# JETSON_V2.net
KiCad netlist of a schematic drawn in Altium Designer
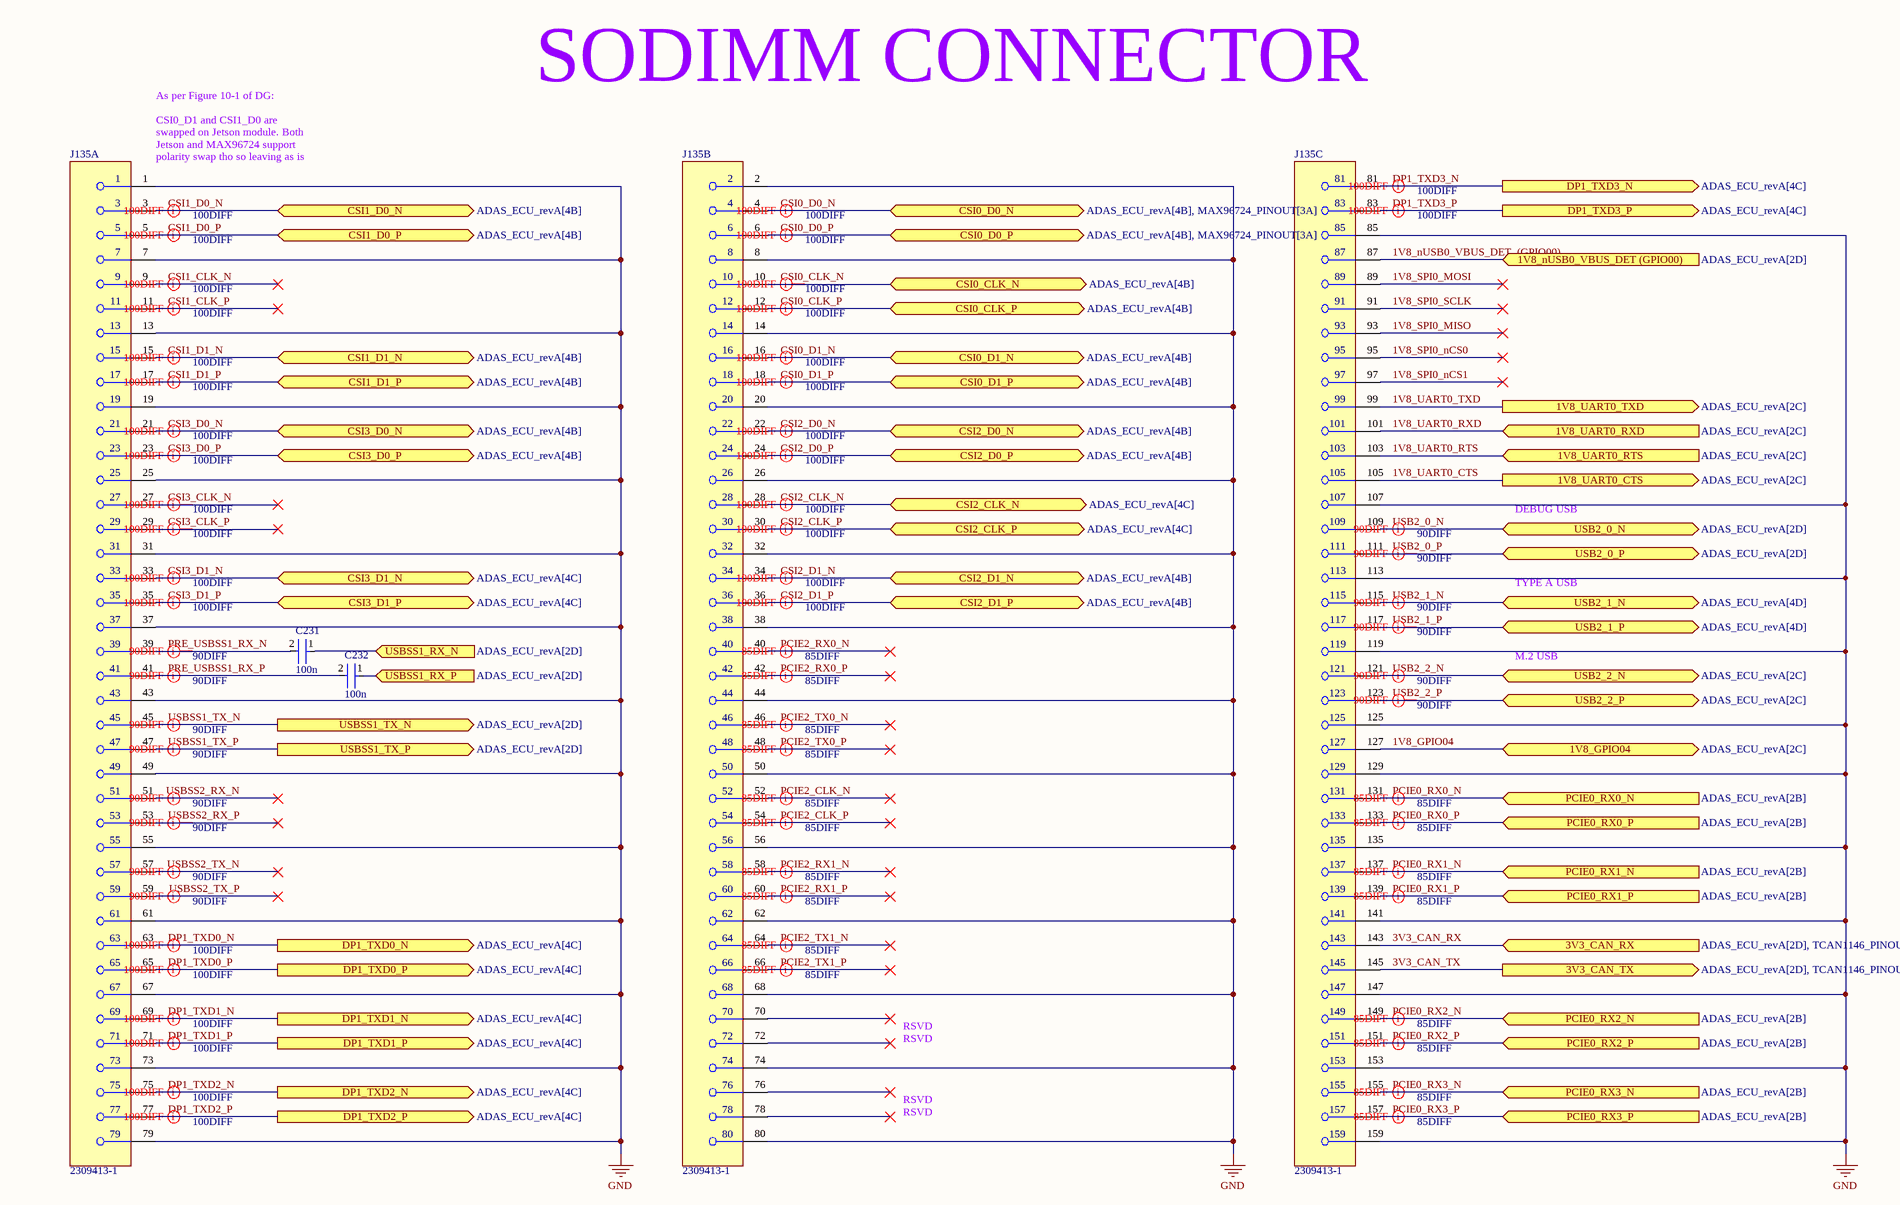
[diagram p0: JETSON_V2.SchDoc, top left]
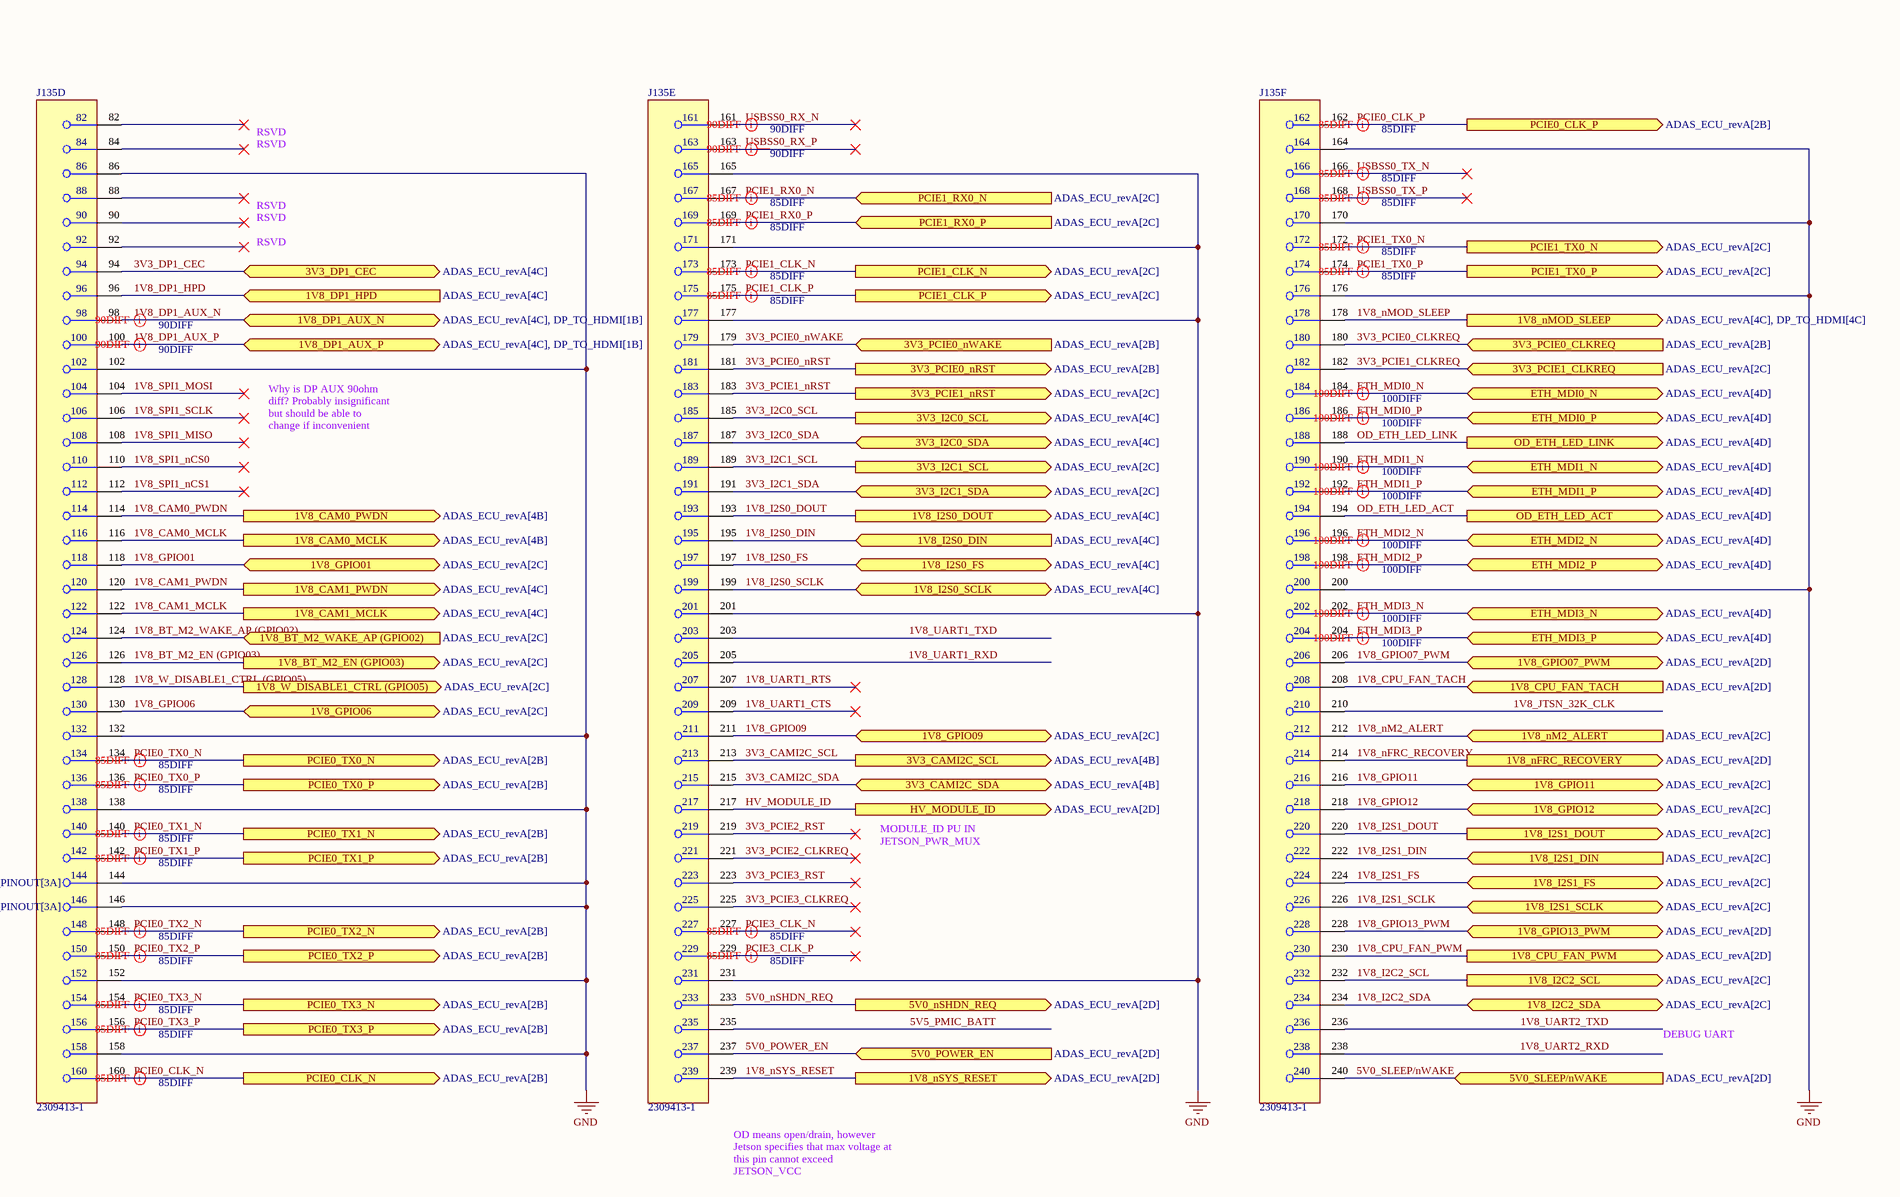
[diagram p1: JETSON_V2.SchDoc, top right]
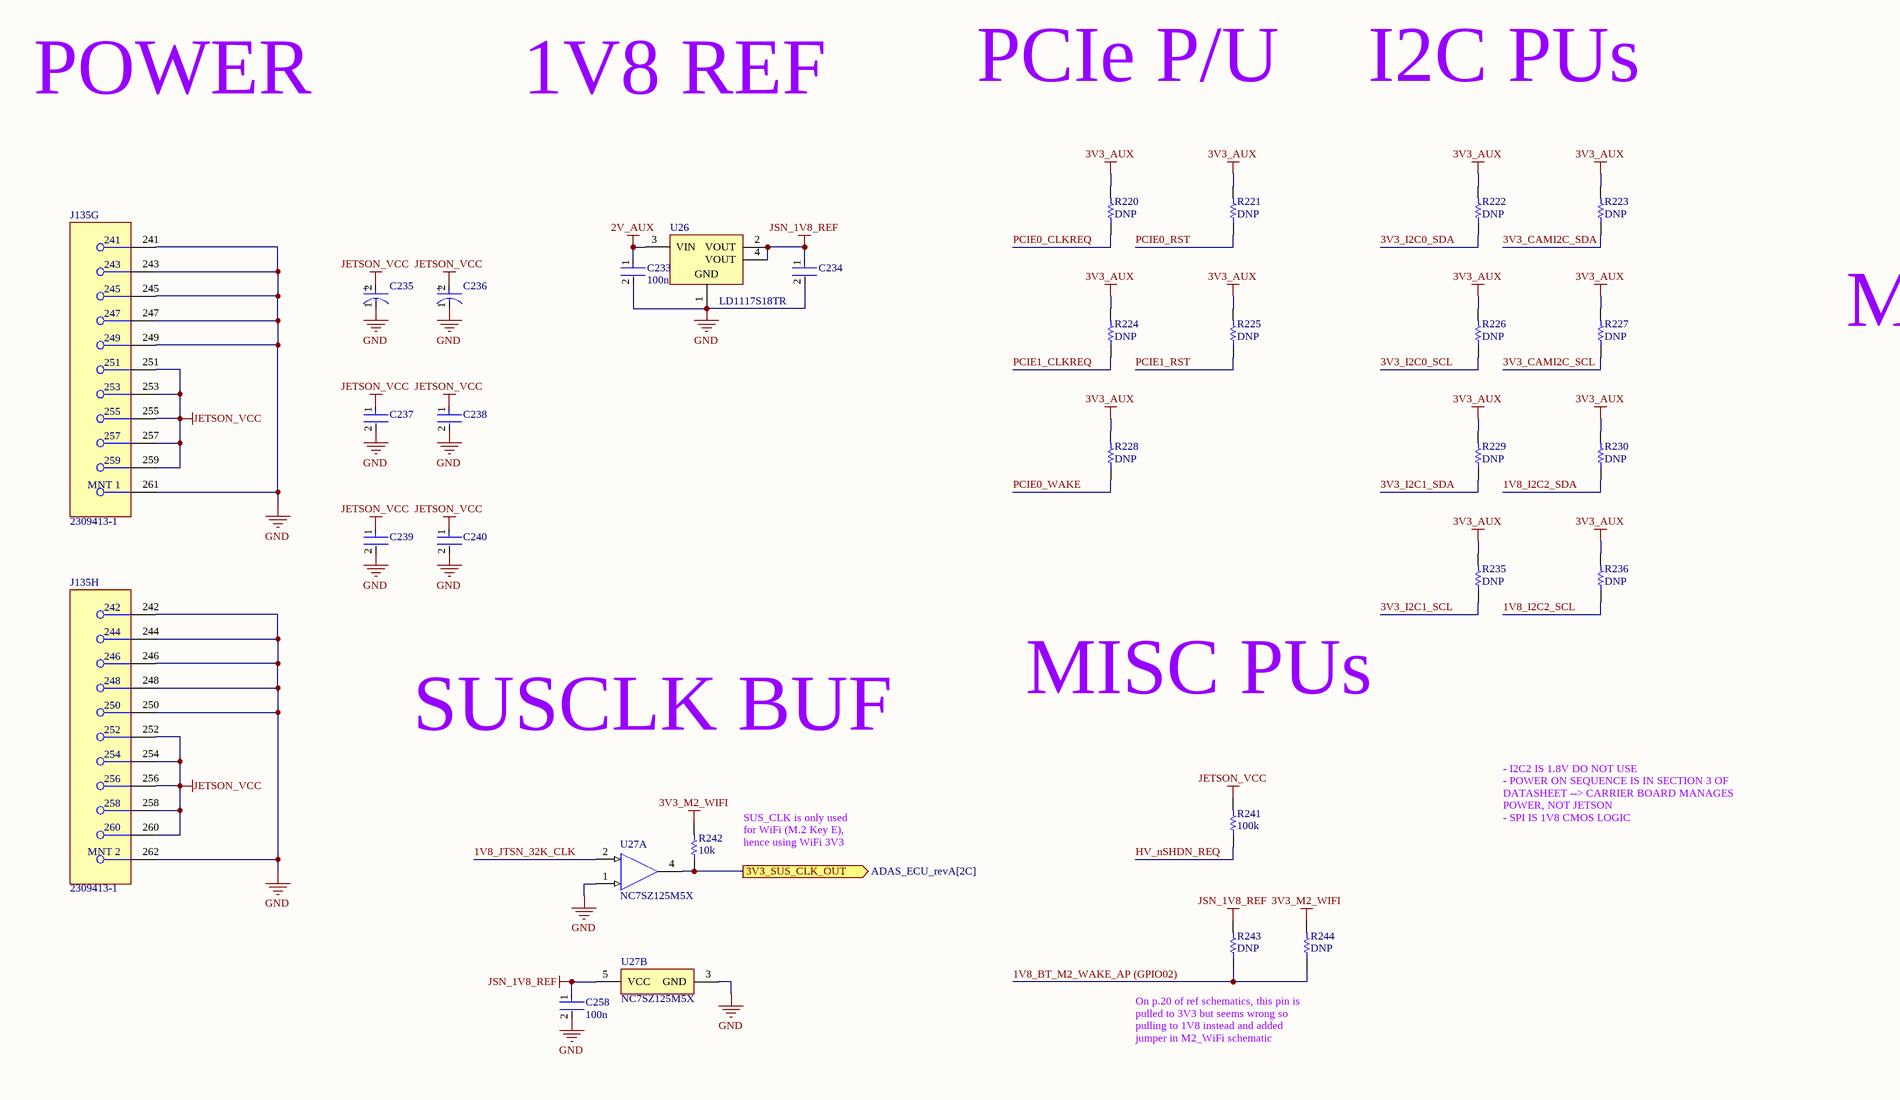
[diagram p2: JETSON_V2.SchDoc, bottom left]
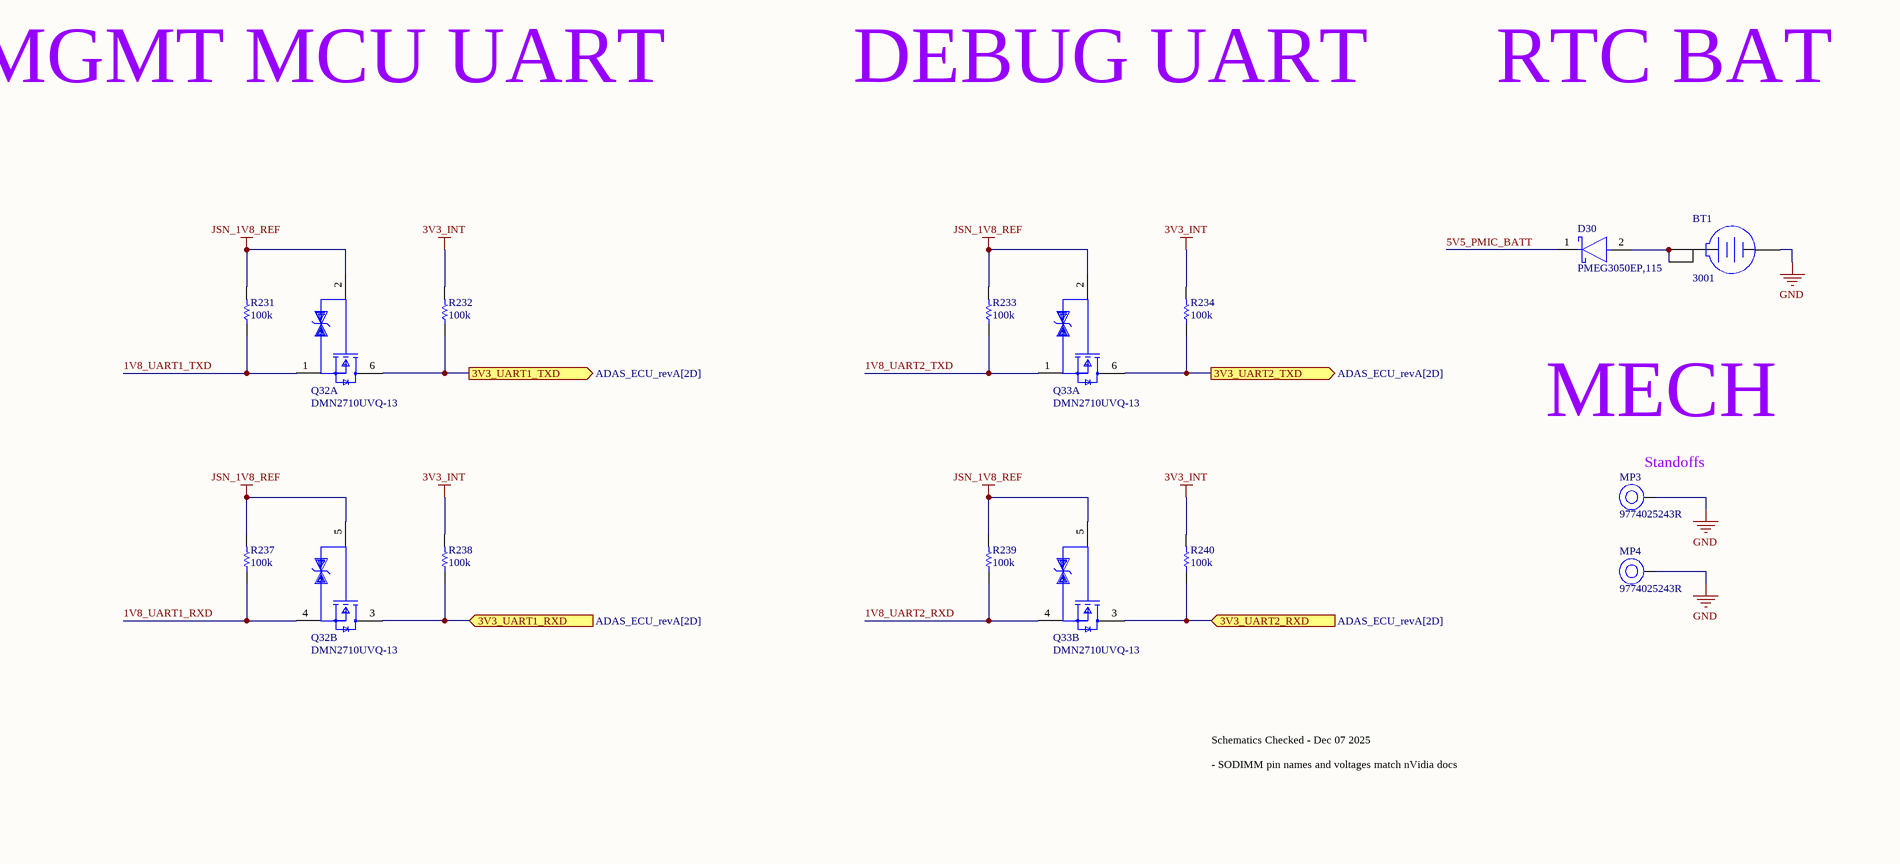
[diagram p3: JETSON_V2.SchDoc, bottom right]

(export (version "E")
  (design (tool "Eeschema 10.0.6"))
  (components
    (comp (ref "BT1")
      (value "3001")
      (footprint "KSTN-3001_V")
      (description "Holder Battery Coin, 12 mm, 2-Pin THD, RoHS")
      (fields (field (name "MANUFACTURER") "Keystone"))
      (libsource (lib "Altium Content Vault") (part "BATTERY-HOLDER-COIN-3"))
    )
    (comp (ref "C231")
      (value "100n")
      (footprint "FP-0402-L_1_0_0_05-W_0_5-IPC_A")
      (description "LARGE PADS, 0402 CAP, CHANGE COMMENT TO MATCH REAL P/N")
      (libsource (lib "Space Concordia") (part "b4654b650e69147ec39a6b967a45e02"))
    )
    (comp (ref "C232")
      (value "100n")
      (footprint "FP-0402-L_1_0_0_05-W_0_5-IPC_A")
      (description "LARGE PADS, 0402 CAP, CHANGE COMMENT TO MATCH REAL P/N")
      (libsource (lib "Space Concordia") (part "b4654b650e69147ec39a6b967a45e02"))
    )
    (comp (ref "C233")
      (value "100n")
      (footprint "FP-0402-L_1_0_0_05-W_0_5-IPC_A")
      (description "LARGE PADS, 0402 CAP, CHANGE COMMENT TO MATCH REAL P/N")
      (libsource (lib "Space Concordia") (part "b4654b650e69147ec39a6b967a45e02"))
    )
    (comp (ref "C234")
      (value "GRM188R60J106ME47D")
      (footprint "FP-GRM188-0_1-e0_2_0_55-IPC_A")
      (description "Chip Multilayer Ceramic Capacitors for General Purpose, 0603, 10uF, X5R, 15%, 20%, 6.3V")
      (fields (field (name "VOLTAGE") "6.3V") (field (name "TOLERANCE") "20%"))
      (libsource (lib "Altium Content Vault") (part "02cd4be3c70576c341d710602a673aa"))
    )
    (comp (ref "C235")
      (value "T491X107K025AT")
      (footprint "FP-T491X107K025AT-MFG")
      (description "CAP TANT 100UF 10% 25V 2917")
      (fields (field (name "TOLERANCE") "10%") (field (name "VOLTAGE") "25V"))
      (libsource (lib "Altium Content Vault") (part "cf48714ba7e38822c1575c7ec0b6d1f"))
    )
    (comp (ref "C236")
      (value "T491X107K025AT")
      (footprint "FP-T491X107K025AT-MFG")
      (description "CAP TANT 100UF 10% 25V 2917")
      (fields (field (name "TOLERANCE") "10%") (field (name "VOLTAGE") "25V"))
      (libsource (lib "Altium Content Vault") (part "cf48714ba7e38822c1575c7ec0b6d1f"))
    )
    (comp (ref "C237")
      (value "C3225X7R1H106M250AC")
      (footprint "FP-C3225-250-0_4-MFG")
      (description "Multilayer Ceramic Capacitors 10uF ±20% 50V X7R SMD 1210")
      (fields (field (name "TOLERANCE") "20%"))
      (libsource (lib "Altium Content Vault") (part "02cd4be3c70576c341d710602a673aa"))
    )
    (comp (ref "C238")
      (value "C3225X7R1H106M250AC")
      (footprint "FP-C3225-250-0_4-MFG")
      (description "Multilayer Ceramic Capacitors 10uF ±20% 50V X7R SMD 1210")
      (fields (field (name "TOLERANCE") "20%"))
      (libsource (lib "Altium Content Vault") (part "02cd4be3c70576c341d710602a673aa"))
    )
    (comp (ref "C239")
      (value "C3225X7R1H106M250AC")
      (footprint "FP-C3225-250-0_4-MFG")
      (description "Multilayer Ceramic Capacitors 10uF ±20% 50V X7R SMD 1210")
      (fields (field (name "TOLERANCE") "20%"))
      (libsource (lib "Altium Content Vault") (part "02cd4be3c70576c341d710602a673aa"))
    )
    (comp (ref "C240")
      (value "C3225X7R1H106M250AC")
      (footprint "FP-C3225-250-0_4-MFG")
      (description "Multilayer Ceramic Capacitors 10uF ±20% 50V X7R SMD 1210")
      (fields (field (name "TOLERANCE") "20%"))
      (libsource (lib "Altium Content Vault") (part "02cd4be3c70576c341d710602a673aa"))
    )
    (comp (ref "C258")
      (value "100n")
      (footprint "FP-0402-L_1_0_0_05-W_0_5-IPC_A")
      (description "LARGE PADS, 0402 CAP, CHANGE COMMENT TO MATCH REAL P/N")
      (libsource (lib "Space Concordia") (part "b4654b650e69147ec39a6b967a45e02"))
    )
    (comp (ref "D30")
      (value "PMEG3050EP,115")
      (footprint "FP-SOD128-MFG")
      (description "DIODE SCHOTTKY 30V 5A SOD128")
      (libsource (lib "Altium Content Vault") (part "1d6ec82d83fb6aee721767c19dac4b9"))
    )
    (comp (ref "J135")
      (value "2309413-1")
      (footprint "FP-2309413-1-MFG")
      (description "DDR4 SODIMM 260P 9.2H STD")
      (fields
        (field (name "OCTOPART") "https://octopart.com/2309413-1-te+connectivity-84799194")
        (field (name "MANUFACTURER") "TE Connectivity")
      )
      (libsource (lib "Altium Content Vault") (part "4d1075b24ee2591bdcd47d674b3d2aa"))
    )
    (comp (ref "MP3")
      (value "9774025243R")
      (footprint "9774025243")
      (description "9774025243R Spacer Material: Steel, Tin-Plated Mounting: SMT Series: WA-SMST Thread D: M2")
      (libsource (lib "Altium Content Vault") (part "Spacer"))
    )
    (comp (ref "MP4")
      (value "9774025243R")
      (footprint "9774025243")
      (description "9774025243R Spacer Material: Steel, Tin-Plated Mounting: SMT Series: WA-SMST Thread D: M2")
      (libsource (lib "Altium Content Vault") (part "Spacer"))
    )
    (comp (ref "Q32")
      (value "DMN2710UVQ-13")
      (footprint "SOTFL50P162X60-6N")
      (description "MOSFET Array, Dual N Channel, 20 V, 920 mA, 450 Milliohms, SOT-563, 6 Pins")
      (libsource (lib "Space Concordia") (part "DMN2710UVQ-13"))
    )
    (comp (ref "Q33")
      (value "DMN2710UVQ-13")
      (footprint "SOTFL50P162X60-6N")
      (description "MOSFET Array, Dual N Channel, 20 V, 920 mA, 450 Milliohms, SOT-563, 6 Pins")
      (libsource (lib "Space Concordia") (part "DMN2710UVQ-13"))
    )
    (comp (ref "R220")
      (value "DNP")
      (footprint "R0603B")
      (description "Resistor")
      (libsource (lib "Space Concordia") (part "Resistor"))
    )
    (comp (ref "R221")
      (value "DNP")
      (footprint "R0603B")
      (description "Resistor")
      (libsource (lib "Space Concordia") (part "Resistor"))
    )
    (comp (ref "R222")
      (value "DNP")
      (footprint "R0603B")
      (description "Resistor")
      (libsource (lib "Space Concordia") (part "Resistor"))
    )
    (comp (ref "R223")
      (value "DNP")
      (footprint "R0603B")
      (description "Resistor")
      (libsource (lib "Space Concordia") (part "Resistor"))
    )
    (comp (ref "R224")
      (value "DNP")
      (footprint "R0603B")
      (description "Resistor")
      (libsource (lib "Space Concordia") (part "Resistor"))
    )
    (comp (ref "R225")
      (value "DNP")
      (footprint "R0603B")
      (description "Resistor")
      (libsource (lib "Space Concordia") (part "Resistor"))
    )
    (comp (ref "R226")
      (value "DNP")
      (footprint "R0603B")
      (description "Resistor")
      (libsource (lib "Space Concordia") (part "Resistor"))
    )
    (comp (ref "R227")
      (value "DNP")
      (footprint "R0603B")
      (description "Resistor")
      (libsource (lib "Space Concordia") (part "Resistor"))
    )
    (comp (ref "R228")
      (value "DNP")
      (footprint "R0603B")
      (description "Resistor")
      (libsource (lib "Space Concordia") (part "Resistor"))
    )
    (comp (ref "R229")
      (value "DNP")
      (footprint "R0603B")
      (description "Resistor")
      (libsource (lib "Space Concordia") (part "Resistor"))
    )
    (comp (ref "R230")
      (value "DNP")
      (footprint "R0603B")
      (description "Resistor")
      (libsource (lib "Space Concordia") (part "Resistor"))
    )
    (comp (ref "R231")
      (value "100k")
      (footprint "R0603B")
      (description "Resistor")
      (libsource (lib "Space Concordia") (part "Resistor"))
    )
    (comp (ref "R232")
      (value "100k")
      (footprint "R0603B")
      (description "Resistor")
      (libsource (lib "Space Concordia") (part "Resistor"))
    )
    (comp (ref "R233")
      (value "100k")
      (footprint "R0603B")
      (description "Resistor")
      (libsource (lib "Space Concordia") (part "Resistor"))
    )
    (comp (ref "R234")
      (value "100k")
      (footprint "R0603B")
      (description "Resistor")
      (libsource (lib "Space Concordia") (part "Resistor"))
    )
    (comp (ref "R235")
      (value "DNP")
      (footprint "R0603B")
      (description "Resistor")
      (libsource (lib "Space Concordia") (part "Resistor"))
    )
    (comp (ref "R236")
      (value "DNP")
      (footprint "R0603B")
      (description "Resistor")
      (libsource (lib "Space Concordia") (part "Resistor"))
    )
    (comp (ref "R237")
      (value "100k")
      (footprint "R0603B")
      (description "Resistor")
      (libsource (lib "Space Concordia") (part "Resistor"))
    )
    (comp (ref "R238")
      (value "100k")
      (footprint "R0603B")
      (description "Resistor")
      (libsource (lib "Space Concordia") (part "Resistor"))
    )
    (comp (ref "R239")
      (value "100k")
      (footprint "R0603B")
      (description "Resistor")
      (libsource (lib "Space Concordia") (part "Resistor"))
    )
    (comp (ref "R240")
      (value "100k")
      (footprint "R0603B")
      (description "Resistor")
      (libsource (lib "Space Concordia") (part "Resistor"))
    )
    (comp (ref "R241")
      (value "100k")
      (footprint "R0603B")
      (description "Resistor")
      (libsource (lib "Space Concordia") (part "Resistor"))
    )
    (comp (ref "R242")
      (value "10k")
      (footprint "R0603B")
      (description "Resistor")
      (libsource (lib "Space Concordia") (part "Resistor"))
    )
    (comp (ref "R243")
      (value "DNP")
      (footprint "R0603B")
      (description "Resistor")
      (libsource (lib "Space Concordia") (part "Resistor"))
    )
    (comp (ref "R244")
      (value "DNP")
      (footprint "R0603B")
      (description "Resistor")
      (libsource (lib "Space Concordia") (part "Resistor"))
    )
    (comp (ref "U26")
      (value "LD1117S18TR")
      (footprint "SOT-223_M")
      (description "Fixed Low Drop Positive Voltage Regulator, 1.8V, 4-Pin SOT-223, Tape and Reel")
      (libsource (lib "Altium Content Vault") (part "PM-REG-LD1117-SOT4"))
    )
    (comp (ref "U27")
      (value "NC7SZ125M5X")
      (footprint "FAIR-SOT23-5_V")
      (fields (field (name "MANUFACTURER") "Fairchild Semiconductor"))
      (libsource (lib "Altium Content Vault") (part "FAIR-NC7SZ125-SOT23-5"))
    )
  )
  (nets
    (net (code "1") (name "/1V8_BT_M2_EN (GPIO03)") (class "Default")
      (node (ref "J135") (pin "126") (pinfunction "126_126") (pintype "passive"))
    )
    (net (code "2") (name "/1V8_BT_M2_WAKE_AP (GPIO02)") (class "Default")
      (node (ref "J135") (pin "124") (pinfunction "124_124") (pintype "passive"))
      (node (ref "R243") (pin "1") (pinfunction "1_1") (pintype "passive"))
      (node (ref "R244") (pin "1") (pinfunction "1_1") (pintype "passive"))
    )
    (net (code "3") (name "/1V8_CAM0_MCLK") (class "Default")
      (node (ref "J135") (pin "116") (pinfunction "116_116") (pintype "passive"))
    )
    (net (code "4") (name "/1V8_CAM0_PWDN") (class "Default")
      (node (ref "J135") (pin "114") (pinfunction "114_114") (pintype "passive"))
    )
    (net (code "5") (name "/1V8_CAM1_MCLK") (class "Default")
      (node (ref "J135") (pin "122") (pinfunction "122_122") (pintype "passive"))
    )
    (net (code "6") (name "/1V8_CAM1_PWDN") (class "Default")
      (node (ref "J135") (pin "120") (pinfunction "120_120") (pintype "passive"))
    )
    (net (code "7") (name "/1V8_CPU_FAN_PWM") (class "Default")
      (node (ref "J135") (pin "230") (pinfunction "230_230") (pintype "passive"))
    )
    (net (code "8") (name "/1V8_CPU_FAN_TACH") (class "Default")
      (node (ref "J135") (pin "208") (pinfunction "208_208") (pintype "passive"))
    )
    (net (code "9") (name "/1V8_DP1_AUX_N") (class "Default")
      (node (ref "J135") (pin "98") (pinfunction "98_98") (pintype "passive"))
    )
    (net (code "10") (name "/1V8_DP1_AUX_P") (class "Default")
      (node (ref "J135") (pin "100") (pinfunction "100_100") (pintype "passive"))
    )
    (net (code "11") (name "/1V8_DP1_HPD") (class "Default")
      (node (ref "J135") (pin "96") (pinfunction "96_96") (pintype "passive"))
    )
    (net (code "12") (name "/1V8_GPIO01") (class "Default")
      (node (ref "J135") (pin "118") (pinfunction "118_118") (pintype "passive"))
    )
    (net (code "13") (name "/1V8_GPIO04") (class "Default")
      (node (ref "J135") (pin "127") (pinfunction "127_127") (pintype "passive"))
    )
    (net (code "14") (name "/1V8_GPIO06") (class "Default")
      (node (ref "J135") (pin "130") (pinfunction "130_130") (pintype "passive"))
    )
    (net (code "15") (name "/1V8_GPIO07_PWM") (class "Default")
      (node (ref "J135") (pin "206") (pinfunction "206_206") (pintype "passive"))
    )
    (net (code "16") (name "/1V8_GPIO09") (class "Default")
      (node (ref "J135") (pin "211") (pinfunction "211_211") (pintype "passive"))
    )
    (net (code "17") (name "/1V8_GPIO11") (class "Default")
      (node (ref "J135") (pin "216") (pinfunction "216_216") (pintype "passive"))
    )
    (net (code "18") (name "/1V8_GPIO12") (class "Default")
      (node (ref "J135") (pin "218") (pinfunction "218_218") (pintype "passive"))
    )
    (net (code "19") (name "/1V8_GPIO13_PWM") (class "Default")
      (node (ref "J135") (pin "228") (pinfunction "228_228") (pintype "passive"))
    )
    (net (code "20") (name "/1V8_I2C2_SCL") (class "Default")
      (node (ref "J135") (pin "232") (pinfunction "232_232") (pintype "passive"))
      (node (ref "R236") (pin "1") (pinfunction "1_1") (pintype "passive"))
    )
    (net (code "21") (name "/1V8_I2C2_SDA") (class "Default")
      (node (ref "J135") (pin "234") (pinfunction "234_234") (pintype "passive"))
      (node (ref "R230") (pin "1") (pinfunction "1_1") (pintype "passive"))
    )
    (net (code "22") (name "/1V8_I2S0_DIN") (class "Default")
      (node (ref "J135") (pin "195") (pinfunction "195_195") (pintype "passive"))
    )
    (net (code "23") (name "/1V8_I2S0_DOUT") (class "Default")
      (node (ref "J135") (pin "193") (pinfunction "193_193") (pintype "passive"))
    )
    (net (code "24") (name "/1V8_I2S0_FS") (class "Default")
      (node (ref "J135") (pin "197") (pinfunction "197_197") (pintype "passive"))
    )
    (net (code "25") (name "/1V8_I2S0_SCLK") (class "Default")
      (node (ref "J135") (pin "199") (pinfunction "199_199") (pintype "passive"))
    )
    (net (code "26") (name "/1V8_I2S1_DIN") (class "Default")
      (node (ref "J135") (pin "222") (pinfunction "222_222") (pintype "passive"))
    )
    (net (code "27") (name "/1V8_I2S1_DOUT") (class "Default")
      (node (ref "J135") (pin "220") (pinfunction "220_220") (pintype "passive"))
    )
    (net (code "28") (name "/1V8_I2S1_FS") (class "Default")
      (node (ref "J135") (pin "224") (pinfunction "224_224") (pintype "passive"))
    )
    (net (code "29") (name "/1V8_I2S1_SCLK") (class "Default")
      (node (ref "J135") (pin "226") (pinfunction "226_226") (pintype "passive"))
    )
    (net (code "30") (name "/1V8_JTSN_32K_CLK") (class "Default")
      (node (ref "J135") (pin "210") (pinfunction "210_210") (pintype "passive"))
      (node (ref "U27") (pin "2") (pinfunction "A_2") (pintype "input"))
    )
    (net (code "31") (name "/1V8_SPI0_MISO") (class "Default")
      (node (ref "J135") (pin "93") (pinfunction "93_93") (pintype "passive+no_connect"))
    )
    (net (code "32") (name "/1V8_SPI0_MOSI") (class "Default")
      (node (ref "J135") (pin "89") (pinfunction "89_89") (pintype "passive+no_connect"))
    )
    (net (code "33") (name "/1V8_SPI0_SCLK") (class "Default")
      (node (ref "J135") (pin "91") (pinfunction "91_91") (pintype "passive+no_connect"))
    )
    (net (code "34") (name "/1V8_SPI0_nCS0") (class "Default")
      (node (ref "J135") (pin "95") (pinfunction "95_95") (pintype "passive+no_connect"))
    )
    (net (code "35") (name "/1V8_SPI0_nCS1") (class "Default")
      (node (ref "J135") (pin "97") (pinfunction "97_97") (pintype "passive+no_connect"))
    )
    (net (code "36") (name "/1V8_SPI1_MISO") (class "Default")
      (node (ref "J135") (pin "108") (pinfunction "108_108") (pintype "passive+no_connect"))
    )
    (net (code "37") (name "/1V8_SPI1_MOSI") (class "Default")
      (node (ref "J135") (pin "104") (pinfunction "104_104") (pintype "passive+no_connect"))
    )
    (net (code "38") (name "/1V8_SPI1_SCLK") (class "Default")
      (node (ref "J135") (pin "106") (pinfunction "106_106") (pintype "passive+no_connect"))
    )
    (net (code "39") (name "/1V8_SPI1_nCS0") (class "Default")
      (node (ref "J135") (pin "110") (pinfunction "110_110") (pintype "passive+no_connect"))
    )
    (net (code "40") (name "/1V8_SPI1_nCS1") (class "Default")
      (node (ref "J135") (pin "112") (pinfunction "112_112") (pintype "passive+no_connect"))
    )
    (net (code "41") (name "/1V8_UART0_CTS") (class "Default")
      (node (ref "J135") (pin "105") (pinfunction "105_105") (pintype "passive"))
    )
    (net (code "42") (name "/1V8_UART0_RTS") (class "Default")
      (node (ref "J135") (pin "103") (pinfunction "103_103") (pintype "passive"))
    )
    (net (code "43") (name "/1V8_UART0_RXD") (class "Default")
      (node (ref "J135") (pin "101") (pinfunction "101_101") (pintype "passive"))
    )
    (net (code "44") (name "/1V8_UART0_TXD") (class "Default")
      (node (ref "J135") (pin "99") (pinfunction "99_99") (pintype "passive"))
    )
    (net (code "45") (name "/1V8_UART1_CTS") (class "Default")
      (node (ref "J135") (pin "209") (pinfunction "209_209") (pintype "passive+no_connect"))
    )
    (net (code "46") (name "/1V8_UART1_RTS") (class "Default")
      (node (ref "J135") (pin "207") (pinfunction "207_207") (pintype "passive+no_connect"))
    )
    (net (code "47") (name "/1V8_UART1_RXD") (class "Default")
      (node (ref "J135") (pin "205") (pinfunction "205_205") (pintype "passive"))
      (node (ref "Q32") (pin "4") (pinfunction "Source2_4") (pintype "passive"))
      (node (ref "R237") (pin "1") (pinfunction "1_1") (pintype "passive"))
    )
    (net (code "48") (name "/1V8_UART1_TXD") (class "Default")
      (node (ref "J135") (pin "203") (pinfunction "203_203") (pintype "passive"))
      (node (ref "Q32") (pin "1") (pinfunction "Source1_1") (pintype "passive"))
      (node (ref "R231") (pin "1") (pinfunction "1_1") (pintype "passive"))
    )
    (net (code "49") (name "/1V8_UART2_RXD") (class "Default")
      (node (ref "J135") (pin "238") (pinfunction "238_238") (pintype "passive"))
      (node (ref "Q33") (pin "4") (pinfunction "Source2_4") (pintype "passive"))
      (node (ref "R239") (pin "1") (pinfunction "1_1") (pintype "passive"))
    )
    (net (code "50") (name "/1V8_UART2_TXD") (class "Default")
      (node (ref "J135") (pin "236") (pinfunction "236_236") (pintype "passive"))
      (node (ref "Q33") (pin "1") (pinfunction "Source1_1") (pintype "passive"))
      (node (ref "R233") (pin "1") (pinfunction "1_1") (pintype "passive"))
    )
    (net (code "51") (name "/1V8_W_DISABLE1_CTRL (GPIO05)") (class "Default")
      (node (ref "J135") (pin "128") (pinfunction "128_128") (pintype "passive"))
    )
    (net (code "52") (name "/1V8_nFRC_RECOVERY") (class "Default")
      (node (ref "J135") (pin "214") (pinfunction "214_214") (pintype "passive"))
    )
    (net (code "53") (name "/1V8_nM2_ALERT") (class "Default")
      (node (ref "J135") (pin "212") (pinfunction "212_212") (pintype "passive"))
    )
    (net (code "54") (name "/1V8_nMOD_SLEEP") (class "Default")
      (node (ref "J135") (pin "178") (pinfunction "178_178") (pintype "passive"))
    )
    (net (code "55") (name "/1V8_nSYS_RESET") (class "Default")
      (node (ref "J135") (pin "239") (pinfunction "239_239") (pintype "passive"))
    )
    (net (code "56") (name "/1V8_nUSB0_VBUS_DET  (GPIO00)") (class "Default")
      (node (ref "J135") (pin "87") (pinfunction "87_87") (pintype "passive"))
    )
    (net (code "57") (name "/3V3_CAMI2C_SCL") (class "Default")
      (node (ref "J135") (pin "213") (pinfunction "213_213") (pintype "passive"))
      (node (ref "R227") (pin "1") (pinfunction "1_1") (pintype "passive"))
    )
    (net (code "58") (name "/3V3_CAMI2C_SDA") (class "Default")
      (node (ref "J135") (pin "215") (pinfunction "215_215") (pintype "passive"))
      (node (ref "R223") (pin "1") (pinfunction "1_1") (pintype "passive"))
    )
    (net (code "59") (name "/3V3_CAN_RX") (class "Default")
      (node (ref "J135") (pin "143") (pinfunction "143_143") (pintype "passive"))
    )
    (net (code "60") (name "/3V3_CAN_TX") (class "Default")
      (node (ref "J135") (pin "145") (pinfunction "145_145") (pintype "passive"))
    )
    (net (code "61") (name "/3V3_DP1_CEC") (class "Default")
      (node (ref "J135") (pin "94") (pinfunction "94_94") (pintype "passive"))
    )
    (net (code "62") (name "/3V3_I2C0_SCL") (class "Default")
      (node (ref "J135") (pin "185") (pinfunction "185_185") (pintype "passive"))
      (node (ref "R226") (pin "1") (pinfunction "1_1") (pintype "passive"))
    )
    (net (code "63") (name "/3V3_I2C0_SDA") (class "Default")
      (node (ref "J135") (pin "187") (pinfunction "187_187") (pintype "passive"))
      (node (ref "R222") (pin "1") (pinfunction "1_1") (pintype "passive"))
    )
    (net (code "64") (name "/3V3_I2C1_SCL") (class "Default")
      (node (ref "J135") (pin "189") (pinfunction "189_189") (pintype "passive"))
      (node (ref "R235") (pin "1") (pinfunction "1_1") (pintype "passive"))
    )
    (net (code "65") (name "/3V3_I2C1_SDA") (class "Default")
      (node (ref "J135") (pin "191") (pinfunction "191_191") (pintype "passive"))
      (node (ref "R229") (pin "1") (pinfunction "1_1") (pintype "passive"))
    )
    (net (code "66") (name "/3V3_PCIE0_CLKREQ") (class "Default")
      (node (ref "J135") (pin "180") (pinfunction "180_180") (pintype "passive"))
    )
    (net (code "67") (name "/3V3_PCIE0_nRST") (class "Default")
      (node (ref "J135") (pin "181") (pinfunction "181_181") (pintype "passive"))
    )
    (net (code "68") (name "/3V3_PCIE0_nWAKE") (class "Default")
      (node (ref "J135") (pin "179") (pinfunction "179_179") (pintype "passive"))
    )
    (net (code "69") (name "/3V3_PCIE1_CLKREQ") (class "Default")
      (node (ref "J135") (pin "182") (pinfunction "182_182") (pintype "passive"))
    )
    (net (code "70") (name "/3V3_PCIE1_nRST") (class "Default")
      (node (ref "J135") (pin "183") (pinfunction "183_183") (pintype "passive"))
    )
    (net (code "71") (name "/3V3_PCIE2_CLKREQ") (class "Default")
      (node (ref "J135") (pin "221") (pinfunction "221_221") (pintype "passive+no_connect"))
    )
    (net (code "72") (name "/3V3_PCIE2_RST") (class "Default")
      (node (ref "J135") (pin "219") (pinfunction "219_219") (pintype "passive+no_connect"))
    )
    (net (code "73") (name "/3V3_PCIE3_CLKREQ") (class "Default")
      (node (ref "J135") (pin "225") (pinfunction "225_225") (pintype "passive+no_connect"))
    )
    (net (code "74") (name "/3V3_PCIE3_RST") (class "Default")
      (node (ref "J135") (pin "223") (pinfunction "223_223") (pintype "passive+no_connect"))
    )
    (net (code "75") (name "/3V3_SUS_CLK_OUT") (class "Default")
      (node (ref "R242") (pin "1") (pinfunction "1_1") (pintype "passive"))
      (node (ref "U27") (pin "4") (pinfunction "Y_4") (pintype "tri_state"))
    )
    (net (code "76") (name "/3V3_UART1_RXD") (class "Default")
      (node (ref "Q32") (pin "3") (pinfunction "Drain2_3") (pintype "passive"))
      (node (ref "R238") (pin "1") (pinfunction "1_1") (pintype "passive"))
    )
    (net (code "77") (name "/3V3_UART1_TXD") (class "Default")
      (node (ref "Q32") (pin "6") (pinfunction "Drain1_6") (pintype "passive"))
      (node (ref "R232") (pin "1") (pinfunction "1_1") (pintype "passive"))
    )
    (net (code "78") (name "/3V3_UART2_RXD") (class "Default")
      (node (ref "Q33") (pin "3") (pinfunction "Drain2_3") (pintype "passive"))
      (node (ref "R240") (pin "1") (pinfunction "1_1") (pintype "passive"))
    )
    (net (code "79") (name "/3V3_UART2_TXD") (class "Default")
      (node (ref "Q33") (pin "6") (pinfunction "Drain1_6") (pintype "passive"))
      (node (ref "R234") (pin "1") (pinfunction "1_1") (pintype "passive"))
    )
    (net (code "80") (name "/5V0_POWER_EN") (class "Default")
      (node (ref "J135") (pin "237") (pinfunction "237_237") (pintype "passive"))
    )
    (net (code "81") (name "/5V0_SLEEP{slash}nWAKE") (class "Default")
      (node (ref "J135") (pin "240") (pinfunction "240_240") (pintype "passive"))
    )
    (net (code "82") (name "/5V0_nSHDN_REQ") (class "Default")
      (node (ref "J135") (pin "233") (pinfunction "233_233") (pintype "passive"))
    )
    (net (code "83") (name "/5V5_PMIC_BATT") (class "Default")
      (node (ref "D30") (pin "1") (pinfunction "C_1") (pintype "passive"))
      (node (ref "J135") (pin "235") (pinfunction "235_235") (pintype "passive"))
    )
    (net (code "84") (name "/CSI0_CLK_N") (class "Default")
      (node (ref "J135") (pin "10") (pinfunction "10_10") (pintype "passive"))
    )
    (net (code "85") (name "/CSI0_CLK_P") (class "Default")
      (node (ref "J135") (pin "12") (pinfunction "12_12") (pintype "passive"))
    )
    (net (code "86") (name "/CSI0_D0_N") (class "Default")
      (node (ref "J135") (pin "4") (pinfunction "4_4") (pintype "passive"))
    )
    (net (code "87") (name "/CSI0_D0_P") (class "Default")
      (node (ref "J135") (pin "6") (pinfunction "6_6") (pintype "passive"))
    )
    (net (code "88") (name "/CSI0_D1_N") (class "Default")
      (node (ref "J135") (pin "16") (pinfunction "16_16") (pintype "passive"))
    )
    (net (code "89") (name "/CSI0_D1_P") (class "Default")
      (node (ref "J135") (pin "18") (pinfunction "18_18") (pintype "passive"))
    )
    (net (code "90") (name "/CSI1_CLK_N") (class "Default")
      (node (ref "J135") (pin "9") (pinfunction "9_9") (pintype "passive+no_connect"))
    )
    (net (code "91") (name "/CSI1_CLK_P") (class "Default")
      (node (ref "J135") (pin "11") (pinfunction "11_11") (pintype "passive+no_connect"))
    )
    (net (code "92") (name "/CSI1_D0_N") (class "Default")
      (node (ref "J135") (pin "3") (pinfunction "3_3") (pintype "passive"))
    )
    (net (code "93") (name "/CSI1_D0_P") (class "Default")
      (node (ref "J135") (pin "5") (pinfunction "5_5") (pintype "passive"))
    )
    (net (code "94") (name "/CSI1_D1_N") (class "Default")
      (node (ref "J135") (pin "15") (pinfunction "15_15") (pintype "passive"))
    )
    (net (code "95") (name "/CSI1_D1_P") (class "Default")
      (node (ref "J135") (pin "17") (pinfunction "17_17") (pintype "passive"))
    )
    (net (code "96") (name "/CSI2_CLK_N") (class "Default")
      (node (ref "J135") (pin "28") (pinfunction "28_28") (pintype "passive"))
    )
    (net (code "97") (name "/CSI2_CLK_P") (class "Default")
      (node (ref "J135") (pin "30") (pinfunction "30_30") (pintype "passive"))
    )
    (net (code "98") (name "/CSI2_D0_N") (class "Default")
      (node (ref "J135") (pin "22") (pinfunction "22_22") (pintype "passive"))
    )
    (net (code "99") (name "/CSI2_D0_P") (class "Default")
      (node (ref "J135") (pin "24") (pinfunction "24_24") (pintype "passive"))
    )
    (net (code "100") (name "/CSI2_D1_N") (class "Default")
      (node (ref "J135") (pin "34") (pinfunction "34_34") (pintype "passive"))
    )
    (net (code "101") (name "/CSI2_D1_P") (class "Default")
      (node (ref "J135") (pin "36") (pinfunction "36_36") (pintype "passive"))
    )
    (net (code "102") (name "/CSI3_CLK_N") (class "Default")
      (node (ref "J135") (pin "27") (pinfunction "27_27") (pintype "passive+no_connect"))
    )
    (net (code "103") (name "/CSI3_CLK_P") (class "Default")
      (node (ref "J135") (pin "29") (pinfunction "29_29") (pintype "passive+no_connect"))
    )
    (net (code "104") (name "/CSI3_D0_N") (class "Default")
      (node (ref "J135") (pin "21") (pinfunction "21_21") (pintype "passive"))
    )
    (net (code "105") (name "/CSI3_D0_P") (class "Default")
      (node (ref "J135") (pin "23") (pinfunction "23_23") (pintype "passive"))
    )
    (net (code "106") (name "/CSI3_D1_N") (class "Default")
      (node (ref "J135") (pin "33") (pinfunction "33_33") (pintype "passive"))
    )
    (net (code "107") (name "/CSI3_D1_P") (class "Default")
      (node (ref "J135") (pin "35") (pinfunction "35_35") (pintype "passive"))
    )
    (net (code "108") (name "/DP1_TXD0_N") (class "Default")
      (node (ref "J135") (pin "63") (pinfunction "63_63") (pintype "passive"))
    )
    (net (code "109") (name "/DP1_TXD0_P") (class "Default")
      (node (ref "J135") (pin "65") (pinfunction "65_65") (pintype "passive"))
    )
    (net (code "110") (name "/DP1_TXD1_N") (class "Default")
      (node (ref "J135") (pin "69") (pinfunction "69_69") (pintype "passive"))
    )
    (net (code "111") (name "/DP1_TXD1_P") (class "Default")
      (node (ref "J135") (pin "71") (pinfunction "71_71") (pintype "passive"))
    )
    (net (code "112") (name "/DP1_TXD2_N") (class "Default")
      (node (ref "J135") (pin "75") (pinfunction "75_75") (pintype "passive"))
    )
    (net (code "113") (name "/DP1_TXD2_P") (class "Default")
      (node (ref "J135") (pin "77") (pinfunction "77_77") (pintype "passive"))
    )
    (net (code "114") (name "/DP1_TXD3_N") (class "Default")
      (node (ref "J135") (pin "81") (pinfunction "81_81") (pintype "passive"))
    )
    (net (code "115") (name "/DP1_TXD3_P") (class "Default")
      (node (ref "J135") (pin "83") (pinfunction "83_83") (pintype "passive"))
    )
    (net (code "116") (name "/ETH_MDI0_N") (class "Default")
      (node (ref "J135") (pin "184") (pinfunction "184_184") (pintype "passive"))
    )
    (net (code "117") (name "/ETH_MDI0_P") (class "Default")
      (node (ref "J135") (pin "186") (pinfunction "186_186") (pintype "passive"))
    )
    (net (code "118") (name "/ETH_MDI1_N") (class "Default")
      (node (ref "J135") (pin "190") (pinfunction "190_190") (pintype "passive"))
    )
    (net (code "119") (name "/ETH_MDI1_P") (class "Default")
      (node (ref "J135") (pin "192") (pinfunction "192_192") (pintype "passive"))
    )
    (net (code "120") (name "/ETH_MDI2_N") (class "Default")
      (node (ref "J135") (pin "196") (pinfunction "196_196") (pintype "passive"))
    )
    (net (code "121") (name "/ETH_MDI2_P") (class "Default")
      (node (ref "J135") (pin "198") (pinfunction "198_198") (pintype "passive"))
    )
    (net (code "122") (name "/ETH_MDI3_N") (class "Default")
      (node (ref "J135") (pin "202") (pinfunction "202_202") (pintype "passive"))
    )
    (net (code "123") (name "/ETH_MDI3_P") (class "Default")
      (node (ref "J135") (pin "204") (pinfunction "204_204") (pintype "passive"))
    )
    (net (code "124") (name "/HV_MODULE_ID") (class "Default")
      (node (ref "J135") (pin "217") (pinfunction "217_217") (pintype "passive"))
    )
    (net (code "125") (name "/HV_nSHDN_REQ") (class "Default")
      (node (ref "R241") (pin "1") (pinfunction "1_1") (pintype "passive"))
    )
    (net (code "126") (name "/OD_ETH_LED_ACT") (class "Default")
      (node (ref "J135") (pin "194") (pinfunction "194_194") (pintype "passive"))
    )
    (net (code "127") (name "/OD_ETH_LED_LINK") (class "Default")
      (node (ref "J135") (pin "188") (pinfunction "188_188") (pintype "passive"))
    )
    (net (code "128") (name "/PCIE0_CLKREQ") (class "Default")
      (node (ref "R220") (pin "1") (pinfunction "1_1") (pintype "passive"))
    )
    (net (code "129") (name "/PCIE0_CLK_N") (class "Default")
      (node (ref "J135") (pin "160") (pinfunction "160_160") (pintype "passive"))
    )
    (net (code "130") (name "/PCIE0_CLK_P") (class "Default")
      (node (ref "J135") (pin "162") (pinfunction "162_162") (pintype "passive"))
    )
    (net (code "131") (name "/PCIE0_RST") (class "Default")
      (node (ref "R221") (pin "1") (pinfunction "1_1") (pintype "passive"))
    )
    (net (code "132") (name "/PCIE0_RX0_N") (class "Default")
      (node (ref "J135") (pin "131") (pinfunction "131_131") (pintype "passive"))
    )
    (net (code "133") (name "/PCIE0_RX0_P") (class "Default")
      (node (ref "J135") (pin "133") (pinfunction "133_133") (pintype "passive"))
    )
    (net (code "134") (name "/PCIE0_RX1_N") (class "Default")
      (node (ref "J135") (pin "137") (pinfunction "137_137") (pintype "passive"))
    )
    (net (code "135") (name "/PCIE0_RX1_P") (class "Default")
      (node (ref "J135") (pin "139") (pinfunction "139_139") (pintype "passive"))
    )
    (net (code "136") (name "/PCIE0_RX2_N") (class "Default")
      (node (ref "J135") (pin "149") (pinfunction "149_149") (pintype "passive"))
    )
    (net (code "137") (name "/PCIE0_RX2_P") (class "Default")
      (node (ref "J135") (pin "151") (pinfunction "151_151") (pintype "passive"))
    )
    (net (code "138") (name "/PCIE0_RX3_N") (class "Default")
      (node (ref "J135") (pin "155") (pinfunction "155_155") (pintype "passive"))
    )
    (net (code "139") (name "/PCIE0_RX3_P") (class "Default")
      (node (ref "J135") (pin "157") (pinfunction "157_157") (pintype "passive"))
    )
    (net (code "140") (name "/PCIE0_TX0_N") (class "Default")
      (node (ref "J135") (pin "134") (pinfunction "134_134") (pintype "passive"))
    )
    (net (code "141") (name "/PCIE0_TX0_P") (class "Default")
      (node (ref "J135") (pin "136") (pinfunction "136_136") (pintype "passive"))
    )
    (net (code "142") (name "/PCIE0_TX1_N") (class "Default")
      (node (ref "J135") (pin "140") (pinfunction "140_140") (pintype "passive"))
    )
    (net (code "143") (name "/PCIE0_TX1_P") (class "Default")
      (node (ref "J135") (pin "142") (pinfunction "142_142") (pintype "passive"))
    )
    (net (code "144") (name "/PCIE0_TX2_N") (class "Default")
      (node (ref "J135") (pin "148") (pinfunction "148_148") (pintype "passive"))
    )
    (net (code "145") (name "/PCIE0_TX2_P") (class "Default")
      (node (ref "J135") (pin "150") (pinfunction "150_150") (pintype "passive"))
    )
    (net (code "146") (name "/PCIE0_TX3_N") (class "Default")
      (node (ref "J135") (pin "154") (pinfunction "154_154") (pintype "passive"))
    )
    (net (code "147") (name "/PCIE0_TX3_P") (class "Default")
      (node (ref "J135") (pin "156") (pinfunction "156_156") (pintype "passive"))
    )
    (net (code "148") (name "/PCIE0_WAKE") (class "Default")
      (node (ref "R228") (pin "1") (pinfunction "1_1") (pintype "passive"))
    )
    (net (code "149") (name "/PCIE1_CLKREQ") (class "Default")
      (node (ref "R224") (pin "1") (pinfunction "1_1") (pintype "passive"))
    )
    (net (code "150") (name "/PCIE1_CLK_N") (class "Default")
      (node (ref "J135") (pin "173") (pinfunction "173_173") (pintype "passive"))
    )
    (net (code "151") (name "/PCIE1_CLK_P") (class "Default")
      (node (ref "J135") (pin "175") (pinfunction "175_175") (pintype "passive"))
    )
    (net (code "152") (name "/PCIE1_RST") (class "Default")
      (node (ref "R225") (pin "1") (pinfunction "1_1") (pintype "passive"))
    )
    (net (code "153") (name "/PCIE1_RX0_N") (class "Default")
      (node (ref "J135") (pin "167") (pinfunction "167_167") (pintype "passive"))
    )
    (net (code "154") (name "/PCIE1_RX0_P") (class "Default")
      (node (ref "J135") (pin "169") (pinfunction "169_169") (pintype "passive"))
    )
    (net (code "155") (name "/PCIE1_TX0_N") (class "Default")
      (node (ref "J135") (pin "172") (pinfunction "172_172") (pintype "passive"))
    )
    (net (code "156") (name "/PCIE1_TX0_P") (class "Default")
      (node (ref "J135") (pin "174") (pinfunction "174_174") (pintype "passive"))
    )
    (net (code "157") (name "/PCIE2_CLK_N") (class "Default")
      (node (ref "J135") (pin "52") (pinfunction "52_52") (pintype "passive+no_connect"))
    )
    (net (code "158") (name "/PCIE2_CLK_P") (class "Default")
      (node (ref "J135") (pin "54") (pinfunction "54_54") (pintype "passive+no_connect"))
    )
    (net (code "159") (name "/PCIE2_RX0_N") (class "Default")
      (node (ref "J135") (pin "40") (pinfunction "40_40") (pintype "passive+no_connect"))
    )
    (net (code "160") (name "/PCIE2_RX0_P") (class "Default")
      (node (ref "J135") (pin "42") (pinfunction "42_42") (pintype "passive+no_connect"))
    )
    (net (code "161") (name "/PCIE2_RX1_N") (class "Default")
      (node (ref "J135") (pin "58") (pinfunction "58_58") (pintype "passive+no_connect"))
    )
    (net (code "162") (name "/PCIE2_RX1_P") (class "Default")
      (node (ref "J135") (pin "60") (pinfunction "60_60") (pintype "passive+no_connect"))
    )
    (net (code "163") (name "/PCIE2_TX0_N") (class "Default")
      (node (ref "J135") (pin "46") (pinfunction "46_46") (pintype "passive+no_connect"))
    )
    (net (code "164") (name "/PCIE2_TX0_P") (class "Default")
      (node (ref "J135") (pin "48") (pinfunction "48_48") (pintype "passive+no_connect"))
    )
    (net (code "165") (name "/PCIE2_TX1_N") (class "Default")
      (node (ref "J135") (pin "64") (pinfunction "64_64") (pintype "passive+no_connect"))
    )
    (net (code "166") (name "/PCIE2_TX1_P") (class "Default")
      (node (ref "J135") (pin "66") (pinfunction "66_66") (pintype "passive+no_connect"))
    )
    (net (code "167") (name "/PCIE3_CLK_N") (class "Default")
      (node (ref "J135") (pin "227") (pinfunction "227_227") (pintype "passive+no_connect"))
    )
    (net (code "168") (name "/PCIE3_CLK_P") (class "Default")
      (node (ref "J135") (pin "229") (pinfunction "229_229") (pintype "passive+no_connect"))
    )
    (net (code "169") (name "/PRE_USBSS1_RX_N") (class "Default")
      (node (ref "C231") (pin "2") (pinfunction "2_2") (pintype "passive"))
      (node (ref "J135") (pin "39") (pinfunction "39_39") (pintype "passive"))
    )
    (net (code "170") (name "/PRE_USBSS1_RX_P") (class "Default")
      (node (ref "C232") (pin "2") (pinfunction "2_2") (pintype "passive"))
      (node (ref "J135") (pin "41") (pinfunction "41_41") (pintype "passive"))
    )
    (net (code "171") (name "/USB2_0_N") (class "Default")
      (node (ref "J135") (pin "109") (pinfunction "109_109") (pintype "passive"))
    )
    (net (code "172") (name "/USB2_0_P") (class "Default")
      (node (ref "J135") (pin "111") (pinfunction "111_111") (pintype "passive"))
    )
    (net (code "173") (name "/USB2_1_N") (class "Default")
      (node (ref "J135") (pin "115") (pinfunction "115_115") (pintype "passive"))
    )
    (net (code "174") (name "/USB2_1_P") (class "Default")
      (node (ref "J135") (pin "117") (pinfunction "117_117") (pintype "passive"))
    )
    (net (code "175") (name "/USB2_2_N") (class "Default")
      (node (ref "J135") (pin "121") (pinfunction "121_121") (pintype "passive"))
    )
    (net (code "176") (name "/USB2_2_P") (class "Default")
      (node (ref "J135") (pin "123") (pinfunction "123_123") (pintype "passive"))
    )
    (net (code "177") (name "/USBSS0_RX_N") (class "Default")
      (node (ref "J135") (pin "161") (pinfunction "161_161") (pintype "passive+no_connect"))
    )
    (net (code "178") (name "/USBSS0_RX_P") (class "Default")
      (node (ref "J135") (pin "163") (pinfunction "163_163") (pintype "passive+no_connect"))
    )
    (net (code "179") (name "/USBSS0_TX_N") (class "Default")
      (node (ref "J135") (pin "166") (pinfunction "166_166") (pintype "passive+no_connect"))
    )
    (net (code "180") (name "/USBSS0_TX_P") (class "Default")
      (node (ref "J135") (pin "168") (pinfunction "168_168") (pintype "passive+no_connect"))
    )
    (net (code "181") (name "/USBSS1_RX_N") (class "Default")
      (node (ref "C231") (pin "1") (pinfunction "1_1") (pintype "passive"))
    )
    (net (code "182") (name "/USBSS1_RX_P") (class "Default")
      (node (ref "C232") (pin "1") (pinfunction "1_1") (pintype "passive"))
    )
    (net (code "183") (name "/USBSS1_TX_N") (class "Default")
      (node (ref "J135") (pin "45") (pinfunction "45_45") (pintype "passive"))
    )
    (net (code "184") (name "/USBSS1_TX_P") (class "Default")
      (node (ref "J135") (pin "47") (pinfunction "47_47") (pintype "passive"))
    )
    (net (code "185") (name "/USBSS2_RX_N") (class "Default")
      (node (ref "J135") (pin "51") (pinfunction "51_51") (pintype "passive+no_connect"))
    )
    (net (code "186") (name "/USBSS2_RX_P") (class "Default")
      (node (ref "J135") (pin "53") (pinfunction "53_53") (pintype "passive+no_connect"))
    )
    (net (code "187") (name "/USBSS2_TX_N") (class "Default")
      (node (ref "J135") (pin "57") (pinfunction "57_57") (pintype "passive+no_connect"))
    )
    (net (code "188") (name "/USBSS2_TX_P") (class "Default")
      (node (ref "J135") (pin "59") (pinfunction "59_59") (pintype "passive+no_connect"))
    )
    (net (code "189") (name "2V_AUX") (class "Default")
      (node (ref "C233") (pin "1") (pinfunction "1_1") (pintype "passive"))
      (node (ref "U26") (pin "3") (pinfunction "VIN_3") (pintype "power_in"))
    )
    (net (code "190") (name "3V3_AUX") (class "Default")
      (node (ref "R220") (pin "2") (pinfunction "2_2") (pintype "passive"))
      (node (ref "R221") (pin "2") (pinfunction "2_2") (pintype "passive"))
      (node (ref "R222") (pin "2") (pinfunction "2_2") (pintype "passive"))
      (node (ref "R223") (pin "2") (pinfunction "2_2") (pintype "passive"))
      (node (ref "R224") (pin "2") (pinfunction "2_2") (pintype "passive"))
      (node (ref "R225") (pin "2") (pinfunction "2_2") (pintype "passive"))
      (node (ref "R226") (pin "2") (pinfunction "2_2") (pintype "passive"))
      (node (ref "R227") (pin "2") (pinfunction "2_2") (pintype "passive"))
      (node (ref "R228") (pin "2") (pinfunction "2_2") (pintype "passive"))
      (node (ref "R229") (pin "2") (pinfunction "2_2") (pintype "passive"))
      (node (ref "R230") (pin "2") (pinfunction "2_2") (pintype "passive"))
      (node (ref "R235") (pin "2") (pinfunction "2_2") (pintype "passive"))
      (node (ref "R236") (pin "2") (pinfunction "2_2") (pintype "passive"))
    )
    (net (code "191") (name "3V3_INT") (class "Default")
      (node (ref "R232") (pin "2") (pinfunction "2_2") (pintype "passive"))
      (node (ref "R234") (pin "2") (pinfunction "2_2") (pintype "passive"))
      (node (ref "R238") (pin "2") (pinfunction "2_2") (pintype "passive"))
      (node (ref "R240") (pin "2") (pinfunction "2_2") (pintype "passive"))
    )
    (net (code "192") (name "3V3_M2_WIFI") (class "Default")
      (node (ref "R242") (pin "2") (pinfunction "2_2") (pintype "passive"))
      (node (ref "R244") (pin "2") (pinfunction "2_2") (pintype "passive"))
    )
    (net (code "193") (name "GND") (class "Default")
      (node (ref "BT1") (pin "3") (pinfunction "-_3") (pintype "passive"))
      (node (ref "C233") (pin "2") (pinfunction "2_2") (pintype "passive"))
      (node (ref "C234") (pin "2") (pinfunction "2_2") (pintype "passive"))
      (node (ref "C235") (pin "1") (pinfunction "C_1") (pintype "passive"))
      (node (ref "C236") (pin "1") (pinfunction "C_1") (pintype "passive"))
      (node (ref "C237") (pin "2") (pinfunction "2_2") (pintype "passive"))
      (node (ref "C238") (pin "2") (pinfunction "2_2") (pintype "passive"))
      (node (ref "C239") (pin "2") (pinfunction "2_2") (pintype "passive"))
      (node (ref "C240") (pin "2") (pinfunction "2_2") (pintype "passive"))
      (node (ref "C258") (pin "2") (pinfunction "2_2") (pintype "passive"))
      (node (ref "J135") (pin "1") (pinfunction "1_1") (pintype "passive"))
      (node (ref "J135") (pin "102") (pinfunction "102_102") (pintype "passive"))
      (node (ref "J135") (pin "107") (pinfunction "107_107") (pintype "passive"))
      (node (ref "J135") (pin "113") (pinfunction "113_113") (pintype "passive"))
      (node (ref "J135") (pin "119") (pinfunction "119_119") (pintype "passive"))
      (node (ref "J135") (pin "125") (pinfunction "125_125") (pintype "passive"))
      (node (ref "J135") (pin "129") (pinfunction "129_129") (pintype "passive"))
      (node (ref "J135") (pin "13") (pinfunction "13_13") (pintype "passive"))
      (node (ref "J135") (pin "132") (pinfunction "132_132") (pintype "passive"))
      (node (ref "J135") (pin "135") (pinfunction "135_135") (pintype "passive"))
      (node (ref "J135") (pin "138") (pinfunction "138_138") (pintype "passive"))
      (node (ref "J135") (pin "14") (pinfunction "14_14") (pintype "passive"))
      (node (ref "J135") (pin "141") (pinfunction "141_141") (pintype "passive"))
      (node (ref "J135") (pin "144") (pinfunction "144_144") (pintype "passive"))
      (node (ref "J135") (pin "146") (pinfunction "146_146") (pintype "passive"))
      (node (ref "J135") (pin "147") (pinfunction "147_147") (pintype "passive"))
      (node (ref "J135") (pin "152") (pinfunction "152_152") (pintype "passive"))
      (node (ref "J135") (pin "153") (pinfunction "153_153") (pintype "passive"))
      (node (ref "J135") (pin "158") (pinfunction "158_158") (pintype "passive"))
      (node (ref "J135") (pin "159") (pinfunction "159_159") (pintype "passive"))
      (node (ref "J135") (pin "164") (pinfunction "164_164") (pintype "passive"))
      (node (ref "J135") (pin "165") (pinfunction "165_165") (pintype "passive"))
      (node (ref "J135") (pin "170") (pinfunction "170_170") (pintype "passive"))
      (node (ref "J135") (pin "171") (pinfunction "171_171") (pintype "passive"))
      (node (ref "J135") (pin "176") (pinfunction "176_176") (pintype "passive"))
      (node (ref "J135") (pin "177") (pinfunction "177_177") (pintype "passive"))
      (node (ref "J135") (pin "19") (pinfunction "19_19") (pintype "passive"))
      (node (ref "J135") (pin "2") (pinfunction "2_2") (pintype "passive"))
      (node (ref "J135") (pin "20") (pinfunction "20_20") (pintype "passive"))
      (node (ref "J135") (pin "200") (pinfunction "200_200") (pintype "passive"))
      (node (ref "J135") (pin "201") (pinfunction "201_201") (pintype "passive"))
      (node (ref "J135") (pin "231") (pinfunction "231_231") (pintype "passive"))
      (node (ref "J135") (pin "241") (pinfunction "241_241") (pintype "passive"))
      (node (ref "J135") (pin "242") (pinfunction "242_242") (pintype "passive"))
      (node (ref "J135") (pin "243") (pinfunction "243_243") (pintype "passive"))
      (node (ref "J135") (pin "244") (pinfunction "244_244") (pintype "passive"))
      (node (ref "J135") (pin "245") (pinfunction "245_245") (pintype "passive"))
      (node (ref "J135") (pin "246") (pinfunction "246_246") (pintype "passive"))
      (node (ref "J135") (pin "247") (pinfunction "247_247") (pintype "passive"))
      (node (ref "J135") (pin "248") (pinfunction "248_248") (pintype "passive"))
      (node (ref "J135") (pin "249") (pinfunction "249_249") (pintype "passive"))
      (node (ref "J135") (pin "25") (pinfunction "25_25") (pintype "passive"))
      (node (ref "J135") (pin "250") (pinfunction "250_250") (pintype "passive"))
      (node (ref "J135") (pin "26") (pinfunction "26_26") (pintype "passive"))
      (node (ref "J135") (pin "261") (pinfunction "MNT_1_261") (pintype "passive"))
      (node (ref "J135") (pin "262") (pinfunction "MNT_2_262") (pintype "passive"))
      (node (ref "J135") (pin "31") (pinfunction "31_31") (pintype "passive"))
      (node (ref "J135") (pin "32") (pinfunction "32_32") (pintype "passive"))
      (node (ref "J135") (pin "37") (pinfunction "37_37") (pintype "passive"))
      (node (ref "J135") (pin "38") (pinfunction "38_38") (pintype "passive"))
      (node (ref "J135") (pin "43") (pinfunction "43_43") (pintype "passive"))
      (node (ref "J135") (pin "44") (pinfunction "44_44") (pintype "passive"))
      (node (ref "J135") (pin "49") (pinfunction "49_49") (pintype "passive"))
      (node (ref "J135") (pin "50") (pinfunction "50_50") (pintype "passive"))
      (node (ref "J135") (pin "55") (pinfunction "55_55") (pintype "passive"))
      (node (ref "J135") (pin "56") (pinfunction "56_56") (pintype "passive"))
      (node (ref "J135") (pin "61") (pinfunction "61_61") (pintype "passive"))
      (node (ref "J135") (pin "62") (pinfunction "62_62") (pintype "passive"))
      (node (ref "J135") (pin "67") (pinfunction "67_67") (pintype "passive"))
      (node (ref "J135") (pin "68") (pinfunction "68_68") (pintype "passive"))
      (node (ref "J135") (pin "7") (pinfunction "7_7") (pintype "passive"))
      (node (ref "J135") (pin "73") (pinfunction "73_73") (pintype "passive"))
      (node (ref "J135") (pin "74") (pinfunction "74_74") (pintype "passive"))
      (node (ref "J135") (pin "79") (pinfunction "79_79") (pintype "passive"))
      (node (ref "J135") (pin "8") (pinfunction "8_8") (pintype "passive"))
      (node (ref "J135") (pin "80") (pinfunction "80_80") (pintype "passive"))
      (node (ref "J135") (pin "85") (pinfunction "85_85") (pintype "passive"))
      (node (ref "J135") (pin "86") (pinfunction "86_86") (pintype "passive"))
      (node (ref "MP3") (pin "1") (pinfunction "1_1") (pintype "passive"))
      (node (ref "MP4") (pin "1") (pinfunction "1_1") (pintype "passive"))
      (node (ref "U26") (pin "1") (pinfunction "GND_1") (pintype "power_in"))
      (node (ref "U27") (pin "1") (pinfunction "~{OE}_1") (pintype "input"))
      (node (ref "U27") (pin "3") (pinfunction "GND_3") (pintype "power_in"))
    )
    (net (code "194") (name "JETSON_VCC") (class "Default")
      (node (ref "C235") (pin "2") (pinfunction "A_2") (pintype "passive"))
      (node (ref "C236") (pin "2") (pinfunction "A_2") (pintype "passive"))
      (node (ref "C237") (pin "1") (pinfunction "1_1") (pintype "passive"))
      (node (ref "C238") (pin "1") (pinfunction "1_1") (pintype "passive"))
      (node (ref "C239") (pin "1") (pinfunction "1_1") (pintype "passive"))
      (node (ref "C240") (pin "1") (pinfunction "1_1") (pintype "passive"))
      (node (ref "J135") (pin "251") (pinfunction "251_251") (pintype "passive"))
      (node (ref "J135") (pin "252") (pinfunction "252_252") (pintype "passive"))
      (node (ref "J135") (pin "253") (pinfunction "253_253") (pintype "passive"))
      (node (ref "J135") (pin "254") (pinfunction "254_254") (pintype "passive"))
      (node (ref "J135") (pin "255") (pinfunction "255_255") (pintype "passive"))
      (node (ref "J135") (pin "256") (pinfunction "256_256") (pintype "passive"))
      (node (ref "J135") (pin "257") (pinfunction "257_257") (pintype "passive"))
      (node (ref "J135") (pin "258") (pinfunction "258_258") (pintype "passive"))
      (node (ref "J135") (pin "259") (pinfunction "259_259") (pintype "passive"))
      (node (ref "J135") (pin "260") (pinfunction "260_260") (pintype "passive"))
      (node (ref "R241") (pin "2") (pinfunction "2_2") (pintype "passive"))
    )
    (net (code "195") (name "JSN_1V8_REF") (class "Default")
      (node (ref "C234") (pin "1") (pinfunction "1_1") (pintype "passive"))
      (node (ref "C258") (pin "1") (pinfunction "1_1") (pintype "passive"))
      (node (ref "Q32") (pin "2") (pinfunction "Gate1_2") (pintype "passive"))
      (node (ref "Q32") (pin "5") (pinfunction "Gate2_5") (pintype "passive"))
      (node (ref "Q33") (pin "2") (pinfunction "Gate1_2") (pintype "passive"))
      (node (ref "Q33") (pin "5") (pinfunction "Gate2_5") (pintype "passive"))
      (node (ref "R231") (pin "2") (pinfunction "2_2") (pintype "passive"))
      (node (ref "R233") (pin "2") (pinfunction "2_2") (pintype "passive"))
      (node (ref "R237") (pin "2") (pinfunction "2_2") (pintype "passive"))
      (node (ref "R239") (pin "2") (pinfunction "2_2") (pintype "passive"))
      (node (ref "R243") (pin "2") (pinfunction "2_2") (pintype "passive"))
      (node (ref "U26") (pin "2") (pinfunction "VOUT_2") (pintype "power_in"))
      (node (ref "U26") (pin "4") (pinfunction "VOUT_4") (pintype "power_in"))
      (node (ref "U27") (pin "5") (pinfunction "VCC_5") (pintype "power_in"))
    )
    (net (code "196") (name "Net-(D30-A)") (class "Default")
      (node (ref "BT1") (pin "1") (pinfunction "+_1") (pintype "passive"))
      (node (ref "BT1") (pin "2") (pinfunction "+_2") (pintype "passive"))
      (node (ref "D30") (pin "2") (pinfunction "A_2") (pintype "passive"))
    )
    (net (code "197") (name "unconnected-(J135-Pad70)") (class "Default")
      (node (ref "J135") (pin "70") (pinfunction "70_70") (pintype "passive+no_connect"))
    )
    (net (code "198") (name "unconnected-(J135-Pad72)") (class "Default")
      (node (ref "J135") (pin "72") (pinfunction "72_72") (pintype "passive+no_connect"))
    )
    (net (code "199") (name "unconnected-(J135-Pad76)") (class "Default")
      (node (ref "J135") (pin "76") (pinfunction "76_76") (pintype "passive+no_connect"))
    )
    (net (code "200") (name "unconnected-(J135-Pad78)") (class "Default")
      (node (ref "J135") (pin "78") (pinfunction "78_78") (pintype "passive+no_connect"))
    )
    (net (code "201") (name "unconnected-(J135-Pad82)") (class "Default")
      (node (ref "J135") (pin "82") (pinfunction "82_82") (pintype "passive+no_connect"))
    )
    (net (code "202") (name "unconnected-(J135-Pad84)") (class "Default")
      (node (ref "J135") (pin "84") (pinfunction "84_84") (pintype "passive+no_connect"))
    )
    (net (code "203") (name "unconnected-(J135-Pad88)") (class "Default")
      (node (ref "J135") (pin "88") (pinfunction "88_88") (pintype "passive+no_connect"))
    )
    (net (code "204") (name "unconnected-(J135-Pad90)") (class "Default")
      (node (ref "J135") (pin "90") (pinfunction "90_90") (pintype "passive+no_connect"))
    )
    (net (code "205") (name "unconnected-(J135-Pad92)") (class "Default")
      (node (ref "J135") (pin "92") (pinfunction "92_92") (pintype "passive+no_connect"))
    )
  )
)
